# Connectors.net
KiCad netlist of a schematic drawn in Altium Designer
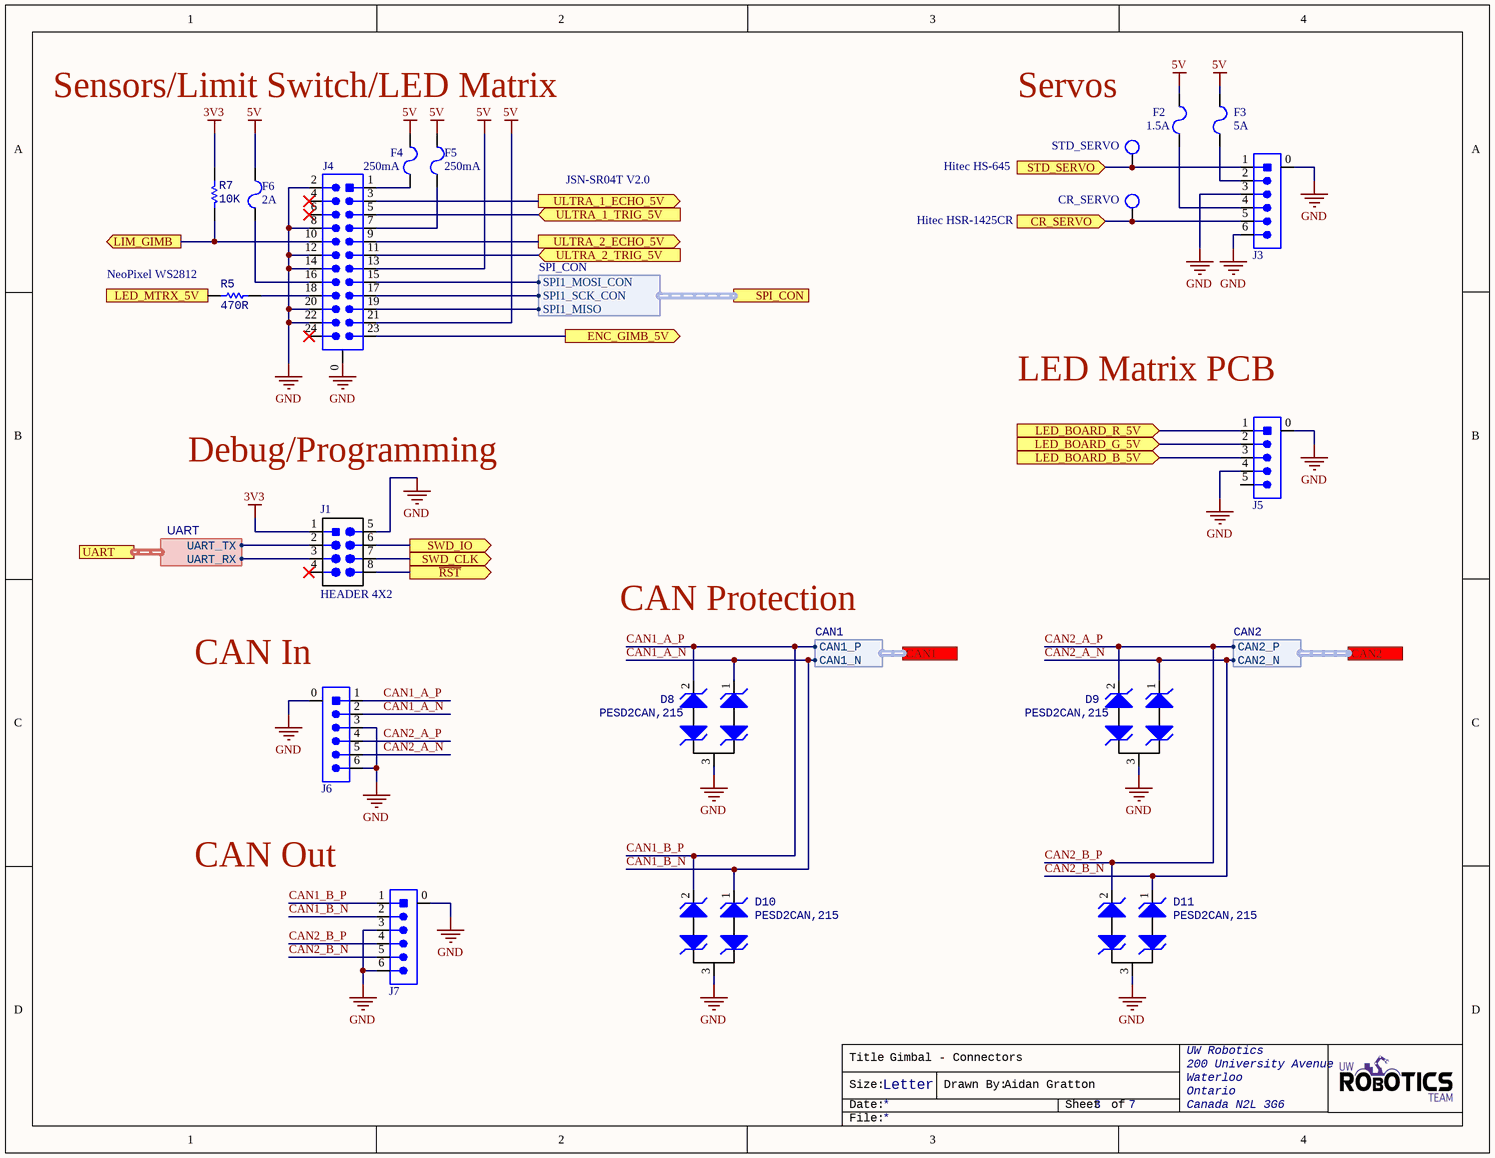
[diagram p0: Connectors.SchDoc]

(export (version "E")
  (design (tool "Eeschema 10.0.6"))
  (components
    (comp (ref "CR_SERVO")
      (value "TESTPOINT_LOOP")
      (footprint "TESTPOINT_LOOP")
      (description "Loop testpoint through-hole pad")
      (fields (field (name "MANUFACTURER") "Keystone Electronics"))
      (libsource (lib "UWRT_Schematic_Library_2020") (part "TESTPOINT_LOOP"))
    )
    (comp (ref "D8")
      (value "TVS_DIODE_CAN")
      (footprint "TVS_DIODE_CAN")
      (description "TVS DIODE 24V 41V SOT323-3")
      (fields
        (field (name "MANUFACTURER") "Nexperia USA Inc.")
        (field (name "MANUFACTURER PART NUMBER") "PESD2CAN,215")
      )
      (libsource (lib "UWRT_Schematic_Library_2020") (part "TVS_DIODE_CAN"))
    )
    (comp (ref "D9")
      (value "TVS_DIODE_CAN")
      (footprint "TVS_DIODE_CAN")
      (description "TVS DIODE 24V 41V SOT323-3")
      (fields
        (field (name "MANUFACTURER") "Nexperia USA Inc.")
        (field (name "MANUFACTURER PART NUMBER") "PESD2CAN,215")
      )
      (libsource (lib "UWRT_Schematic_Library_2020") (part "TVS_DIODE_CAN"))
    )
    (comp (ref "D10")
      (value "TVS_DIODE_CAN")
      (footprint "TVS_DIODE_CAN")
      (description "TVS DIODE 24V 41V SOT323-3")
      (fields
        (field (name "MANUFACTURER") "Nexperia USA Inc.")
        (field (name "MANUFACTURER PART NUMBER") "PESD2CAN,215")
      )
      (libsource (lib "UWRT_Schematic_Library_2020") (part "TVS_DIODE_CAN"))
    )
    (comp (ref "D11")
      (value "TVS_DIODE_CAN")
      (footprint "TVS_DIODE_CAN")
      (description "TVS DIODE 24V 41V SOT323-3")
      (fields
        (field (name "MANUFACTURER") "Nexperia USA Inc.")
        (field (name "MANUFACTURER PART NUMBER") "PESD2CAN,215")
      )
      (libsource (lib "UWRT_Schematic_Library_2020") (part "TVS_DIODE_CAN"))
    )
    (comp (ref "F2")
      (value "FUSE_1.5A_1206")
      (footprint "FUSE_1206")
      (description "FUSE SMD 1.5A 63V")
      (fields (field (name "CURRENT RATING") "1.5A"))
      (libsource (lib "UWRT_Schematic_Library_2020") (part "FUSE_1.5A_1206"))
    )
    (comp (ref "F3")
      (value "FUSE_5A_1206")
      (footprint "FUSE_1206")
      (description "FUSE SMD 5A 63V")
      (fields (field (name "CURRENT RATING") "5A"))
      (libsource (lib "UWRT_Schematic_Library_2020") (part "FUSE_5A_1206"))
    )
    (comp (ref "F4")
      (value "FUSE_250mA_1206")
      (footprint "FUSE_1206")
      (description "FUSE SMD 250mA 125V")
      (fields (field (name "CURRENT RATING") "250mA"))
      (libsource (lib "UWRT_Schematic_Library_2020") (part "FUSE_250mA_1206"))
    )
    (comp (ref "F5")
      (value "FUSE_250mA_1206")
      (footprint "FUSE_1206")
      (description "FUSE SMD 250mA 125V")
      (fields (field (name "CURRENT RATING") "250mA"))
      (libsource (lib "UWRT_Schematic_Library_2020") (part "FUSE_250mA_1206"))
    )
    (comp (ref "F6")
      (value "FUSE_2A_1206")
      (footprint "FUSE_1206")
      (description "FUSE SMD 2A 63V")
      (fields (field (name "CURRENT RATING") "2A"))
      (libsource (lib "UWRT_Schematic_Library_2020") (part "FUSE_2A_1206"))
    )
    (comp (ref "J1")
      (value "HEADER 4X2")
      (footprint "UWRT_Footprint_Library_2019:HEADER_2X4")
      (description "CONN HEADER VERT 8POS 2.54MM")
      (libsource (lib "UWRT_Schematic_Library_2020") (part "HEADER 4X2"))
    )
    (comp (ref "J3")
      (value "CON_6M_SM_RA")
      (footprint "MOLEX-5024940670")
      (description "CONN HEADER SMD RIGHT ANGLE 2MM PITCH")
      (libsource (lib "") (part "CON_6M_SM_RA_1"))
    )
    (comp (ref "J4")
      (value "CON_12x2M_SM_RA")
      (footprint "MOLEX-5031482490")
      (description "CONN HEADER SMD RIGHT ANGLE 1.5MM PITCH")
      (libsource (lib "UWRT_Schematic_Library_2020") (part "CON_12x2M_SM_RA"))
    )
    (comp (ref "J5")
      (value "CON_5M_SM_RA")
      (footprint "MOLEX-5025850570")
      (description "CONN HEADER SMD RIGHT ANGLE 1.5MM PITCH")
      (libsource (lib "UWRT_Schematic_Library_2020") (part "CON_5M_SM_RA"))
    )
    (comp (ref "J6")
      (value "CON_6M_SM_RA")
      (footprint "MOLEX-5024940670")
      (description "CONN HEADER SMD RIGHT ANGLE 2MM PITCH")
      (libsource (lib "UWRT_Schematic_Library_2020") (part "CON_6M_SM_RA"))
    )
    (comp (ref "J7")
      (value "CON_6M_SM_RA")
      (footprint "MOLEX-5024940670")
      (description "CONN HEADER SMD RIGHT ANGLE 2MM PITCH")
      (libsource (lib "") (part "CON_6M_SM_RA_1"))
    )
    (comp (ref "R5")
      (value "470R")
      (footprint "RESC0603(1608)_N")
      (description "RES SMD 470 OHM 1% 1/10W 0603")
      (fields (field (name "MANUFACTURER") "Yageo") (field (name "MPN") "AC0603FR-07470RL"))
      (libsource (lib "UWRT_Schematic_Library_2020") (part "RES_470R_0603"))
    )
    (comp (ref "R7")
      (value "10K")
      (footprint "RESC0603(1608)_N")
      (description "RES SMD 10K OHM 5% 1/10W 0603")
      (fields (field (name "MANUFACTURER") "Yageo") (field (name "TOLERANCE") "5%"))
      (libsource (lib "UWRT_Schematic_Library_2020") (part "RES_10K_0603"))
    )
    (comp (ref "STD_SERVO")
      (value "TESTPOINT_LOOP")
      (footprint "TESTPOINT_LOOP")
      (description "Loop testpoint through-hole pad")
      (fields (field (name "MANUFACTURER") "Keystone Electronics"))
      (libsource (lib "UWRT_Schematic_Library_2020") (part "TESTPOINT_LOOP"))
    )
  )
  (nets
    (net (code "5") (name "/CAN1_A_N") (class "Default")
      (node (ref "D10") (pin "1") (pinfunction "1_1") (pintype "passive"))
      (node (ref "D8") (pin "1") (pinfunction "1_1") (pintype "passive"))
      (node (ref "J6") (pin "2") (pinfunction "2_2") (pintype "passive"))
      (node (ref "J7") (pin "2") (pinfunction "2_2") (pintype "passive"))
    )
    (net (code "6") (name "/CAN1_A_P") (class "Default")
      (node (ref "D10") (pin "2") (pinfunction "2_2") (pintype "passive"))
      (node (ref "D8") (pin "2") (pinfunction "2_2") (pintype "passive"))
      (node (ref "J6") (pin "1") (pinfunction "1_1") (pintype "passive"))
      (node (ref "J7") (pin "1") (pinfunction "1_1") (pintype "passive"))
    )
    (net (code "7") (name "/CAN2_A_N") (class "Default")
      (node (ref "D11") (pin "1") (pinfunction "1_1") (pintype "passive"))
      (node (ref "D9") (pin "1") (pinfunction "1_1") (pintype "passive"))
      (node (ref "J6") (pin "5") (pinfunction "5_5") (pintype "passive"))
      (node (ref "J7") (pin "5") (pinfunction "5_5") (pintype "passive"))
    )
    (net (code "8") (name "/CAN2_A_P") (class "Default")
      (node (ref "D11") (pin "2") (pinfunction "2_2") (pintype "passive"))
      (node (ref "D9") (pin "2") (pinfunction "2_2") (pintype "passive"))
      (node (ref "J6") (pin "4") (pinfunction "4_4") (pintype "passive"))
      (node (ref "J7") (pin "4") (pinfunction "4_4") (pintype "passive"))
    )
    (net (code "9") (name "/CR_SERVO") (class "Default")
      (node (ref "CR_SERVO") (pin "1") (pintype "passive"))
      (node (ref "J3") (pin "5") (pinfunction "5_5") (pintype "passive"))
    )
    (net (code "10") (name "/ENC_GIMB_5V") (class "Default")
      (node (ref "J4") (pin "23") (pinfunction "23_23") (pintype "passive"))
    )
    (net (code "11") (name "/LED_BOARD_B_5V") (class "Default")
      (node (ref "J5") (pin "3") (pinfunction "3_3") (pintype "passive"))
    )
    (net (code "12") (name "/LED_BOARD_G_5V") (class "Default")
      (node (ref "J5") (pin "2") (pinfunction "2_2") (pintype "passive"))
    )
    (net (code "13") (name "/LED_BOARD_R_5V") (class "Default")
      (node (ref "J5") (pin "1") (pinfunction "1_1") (pintype "passive"))
    )
    (net (code "14") (name "/LED_MTRX_5V") (class "Default")
      (node (ref "R5") (pin "1") (pinfunction "1_1") (pintype "passive"))
    )
    (net (code "15") (name "/LIM_GIMB") (class "Default")
      (node (ref "J4") (pin "10") (pinfunction "10_10") (pintype "passive"))
      (node (ref "R7") (pin "1") (pinfunction "1_1") (pintype "passive"))
    )
    (net (code "16") (name "/SPI1_MISO") (class "Default")
      (node (ref "J4") (pin "19") (pinfunction "19_19") (pintype "passive"))
    )
    (net (code "17") (name "/SPI1_MOSI_CON") (class "Default")
      (node (ref "J4") (pin "15") (pinfunction "15_15") (pintype "passive"))
    )
    (net (code "18") (name "/SPI1_SCK_CON") (class "Default")
      (node (ref "J4") (pin "17") (pinfunction "17_17") (pintype "passive"))
    )
    (net (code "19") (name "/STD_SERVO") (class "Default")
      (node (ref "J3") (pin "1") (pinfunction "1_1") (pintype "passive"))
      (node (ref "STD_SERVO") (pin "1") (pintype "passive"))
    )
    (net (code "20") (name "/SWD_CLK") (class "Default")
      (node (ref "J1") (pin "7") (pinfunction "3_7") (pintype "passive"))
    )
    (net (code "21") (name "/SWD_IO") (class "Default")
      (node (ref "J1") (pin "6") (pinfunction "2_6") (pintype "passive"))
    )
    (net (code "22") (name "/UART_RX") (class "Default")
      (node (ref "J1") (pin "3") (pinfunction "3_3") (pintype "passive"))
    )
    (net (code "23") (name "/UART_TX") (class "Default")
      (node (ref "J1") (pin "2") (pinfunction "2_2") (pintype "passive"))
    )
    (net (code "24") (name "/ULTRA_1_ECHO_5V") (class "Default")
      (node (ref "J4") (pin "3") (pinfunction "3_3") (pintype "passive"))
    )
    (net (code "25") (name "/ULTRA_1_TRIG_5V") (class "Default")
      (node (ref "J4") (pin "5") (pinfunction "5_5") (pintype "passive"))
    )
    (net (code "26") (name "/ULTRA_2_ECHO_5V") (class "Default")
      (node (ref "J4") (pin "9") (pinfunction "9_9") (pintype "passive"))
    )
    (net (code "27") (name "/ULTRA_2_TRIG_5V") (class "Default")
      (node (ref "J4") (pin "11") (pinfunction "11_11") (pintype "passive"))
    )
    (net (code "32") (name "/~{RST}") (class "Default")
      (node (ref "J1") (pin "8") (pinfunction "4_8") (pintype "passive"))
    )
    (net (code "33") (name "3V3") (class "Default")
      (node (ref "J1") (pin "1") (pinfunction "VCC_1") (pintype "passive"))
      (node (ref "R7") (pin "2") (pinfunction "2_2") (pintype "passive"))
    )
    (net (code "34") (name "5V") (class "Default")
      (node (ref "F2") (pin "2") (pinfunction "2_2") (pintype "passive"))
      (node (ref "F3") (pin "2") (pinfunction "2_2") (pintype "passive"))
      (node (ref "F4") (pin "1") (pinfunction "1_1") (pintype "passive"))
      (node (ref "F5") (pin "2") (pinfunction "2_2") (pintype "passive"))
      (node (ref "F6") (pin "2") (pinfunction "2_2") (pintype "passive"))
      (node (ref "J4") (pin "13") (pinfunction "13_13") (pintype "passive"))
      (node (ref "J4") (pin "21") (pinfunction "21_21") (pintype "passive"))
    )
    (net (code "35") (name "GND") (class "Default")
      (node (ref "D10") (pin "3") (pinfunction "3_3") (pintype "passive"))
      (node (ref "D11") (pin "3") (pinfunction "3_3") (pintype "passive"))
      (node (ref "D8") (pin "3") (pinfunction "3_3") (pintype "passive"))
      (node (ref "D9") (pin "3") (pinfunction "3_3") (pintype "passive"))
      (node (ref "J1") (pin "5") (pinfunction "GND_5") (pintype "passive"))
      (node (ref "J3") (pin "0") (pinfunction "0_0") (pintype "passive"))
      (node (ref "J3") (pin "3") (pinfunction "3_3") (pintype "passive"))
      (node (ref "J3") (pin "6") (pinfunction "6_6") (pintype "passive"))
      (node (ref "J4") (pin "0") (pinfunction "0_0") (pintype "passive"))
      (node (ref "J4") (pin "12") (pinfunction "12_12") (pintype "passive"))
      (node (ref "J4") (pin "14") (pinfunction "14_14") (pintype "passive"))
      (node (ref "J4") (pin "2") (pinfunction "2_2") (pintype "passive"))
      (node (ref "J4") (pin "20") (pinfunction "20_20") (pintype "passive"))
      (node (ref "J4") (pin "22") (pinfunction "22_22") (pintype "passive"))
      (node (ref "J4") (pin "8") (pinfunction "8_8") (pintype "passive"))
      (node (ref "J5") (pin "0") (pinfunction "0_0") (pintype "passive"))
      (node (ref "J5") (pin "4") (pinfunction "4_4") (pintype "passive"))
      (node (ref "J6") (pin "0") (pinfunction "0_0") (pintype "passive"))
      (node (ref "J6") (pin "3") (pinfunction "3_3") (pintype "passive"))
      (node (ref "J6") (pin "6") (pinfunction "6_6") (pintype "passive"))
      (node (ref "J7") (pin "0") (pinfunction "0_0") (pintype "passive"))
      (node (ref "J7") (pin "3") (pinfunction "3_3") (pintype "passive"))
      (node (ref "J7") (pin "6") (pinfunction "6_6") (pintype "passive"))
    )
    (net (code "36") (name "Net-(F2-Pad1)") (class "Default")
      (node (ref "F2") (pin "1") (pinfunction "1_1") (pintype "passive"))
      (node (ref "J3") (pin "4") (pinfunction "4_4") (pintype "passive"))
    )
    (net (code "37") (name "Net-(F3-Pad1)") (class "Default")
      (node (ref "F3") (pin "1") (pinfunction "1_1") (pintype "passive"))
      (node (ref "J3") (pin "2") (pinfunction "2_2") (pintype "passive"))
    )
    (net (code "38") (name "Net-(F4-Pad2)") (class "Default")
      (node (ref "F4") (pin "2") (pinfunction "2_2") (pintype "passive"))
      (node (ref "J4") (pin "1") (pinfunction "1_1") (pintype "passive"))
    )
    (net (code "39") (name "Net-(F5-Pad1)") (class "Default")
      (node (ref "F5") (pin "1") (pinfunction "1_1") (pintype "passive"))
      (node (ref "J4") (pin "7") (pinfunction "7_7") (pintype "passive"))
    )
    (net (code "40") (name "Net-(F6-Pad1)") (class "Default")
      (node (ref "F6") (pin "1") (pinfunction "1_1") (pintype "passive"))
      (node (ref "J4") (pin "16") (pinfunction "16_16") (pintype "passive"))
    )
    (net (code "41") (name "Net-(J4-Pad18)") (class "Default")
      (node (ref "J4") (pin "18") (pinfunction "18_18") (pintype "passive"))
      (node (ref "R5") (pin "2") (pinfunction "2_2") (pintype "passive"))
    )
    (net (code "42") (name "unconnected-(J1-Pad4)") (class "Default")
      (node (ref "J1") (pin "4") (pinfunction "4_4") (pintype "passive+no_connect"))
    )
    (net (code "43") (name "unconnected-(J4-Pad4)") (class "Default")
      (node (ref "J4") (pin "4") (pinfunction "4_4") (pintype "passive+no_connect"))
    )
    (net (code "44") (name "unconnected-(J4-Pad6)") (class "Default")
      (node (ref "J4") (pin "6") (pinfunction "6_6") (pintype "passive+no_connect"))
    )
    (net (code "45") (name "unconnected-(J4-Pad24)") (class "Default")
      (node (ref "J4") (pin "24") (pinfunction "24_24") (pintype "passive+no_connect"))
    )
    (net (code "46") (name "unconnected-(J5-Pad5)") (class "Default")
      (node (ref "J5") (pin "5") (pinfunction "5_5") (pintype "passive"))
    )
  )
)
